# MCU2_USB.net
KiCad netlist of a schematic drawn in Altium Designer
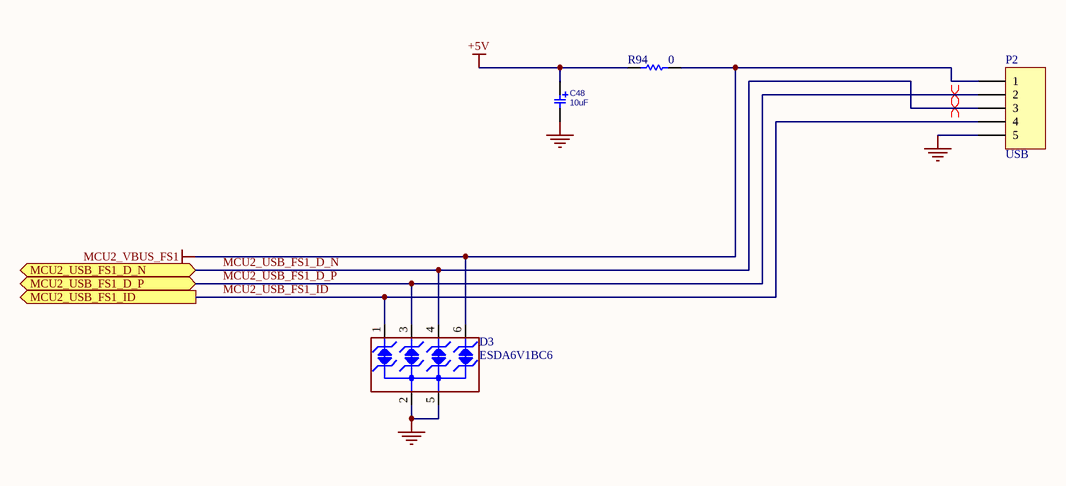
[diagram p0: MCU2_USB.SchDoc]

(export (version "E")
  (design (tool "Eeschema 10.0.6"))
  (components
    (comp (ref "C48")
      (value "10uF")
      (footprint "C_TN_3216")
      (description "CAP, SMD, TAN")
      (fields (field (name "MANF") "VISHAY") (field (name "MANF_P#") "T55A106M6R3C0300"))
      (libsource (lib "CapTantal_passive") (part "CAP_SMD_TAN_10uF_6.3V"))
    )
    (comp (ref "D3")
      (value "ESDA6V1BC6")
      (footprint "samacsys:SOT95P280X145-6N")
      (description "4-line ESD protection")
      (libsource (lib "MB1137") (part "ESDA6V1BC6"))
    )
    (comp (ref "P2")
      (value "USB")
      (footprint "xh-5")
      (description "Header, 5-Pin")
      (fields (field (name "PUBLISHER") "Altium Limited"))
      (libsource (lib "Miscellaneous Connectors") (part "Header 5"))
    )
    (comp (ref "R94")
      (value "0")
      (footprint "R0603E")
      (description "Resistor")
      (fields (field (name "PUBLISHER") "Altium Limited"))
      (libsource (lib "Miscellaneous Devices") (part "Res1"))
    )
  )
  (nets
    (net (code "1") (name "+5V") (class "Default")
      (node (ref "C48") (pin "1") (pinfunction "1_1") (pintype "passive"))
      (node (ref "R94") (pin "2") (pinfunction "2_2") (pintype "passive"))
    )
    (net (code "2") (name "/MCU2_USB_FS1_D_N") (class "Default")
      (node (ref "D3") (pin "4") (pinfunction "IO3_4") (pintype "passive"))
      (node (ref "P2") (pin "3") (pinfunction "3_3") (pintype "passive"))
    )
    (net (code "3") (name "/MCU2_USB_FS1_D_P") (class "Default")
      (node (ref "D3") (pin "3") (pinfunction "GND_3") (pintype "passive"))
      (node (ref "P2") (pin "2") (pinfunction "2_2") (pintype "passive"))
    )
    (net (code "4") (name "/MCU2_USB_FS1_ID") (class "Default")
      (node (ref "D3") (pin "1") (pinfunction "IO1_1") (pintype "passive"))
      (node (ref "P2") (pin "4") (pinfunction "4_4") (pintype "passive"))
    )
    (net (code "5") (name "GND") (class "Default")
      (node (ref "C48") (pin "2") (pinfunction "2_2") (pintype "passive"))
      (node (ref "D3") (pin "2") (pinfunction "IO2_2") (pintype "passive"))
      (node (ref "D3") (pin "5") (pinfunction "IO4_5") (pintype "passive"))
      (node (ref "P2") (pin "5") (pinfunction "5_5") (pintype "passive"))
    )
    (net (code "6") (name "MCU2_VBUS_FS1") (class "Default")
      (node (ref "D3") (pin "6") (pinfunction "NC_6") (pintype "passive"))
      (node (ref "P2") (pin "1") (pinfunction "1_1") (pintype "passive"))
      (node (ref "R94") (pin "1") (pinfunction "1_1") (pintype "passive"))
    )
  )
)
